# DP_current_measure_V3_extension.net
KiCad netlist of a schematic drawn in EAGLE
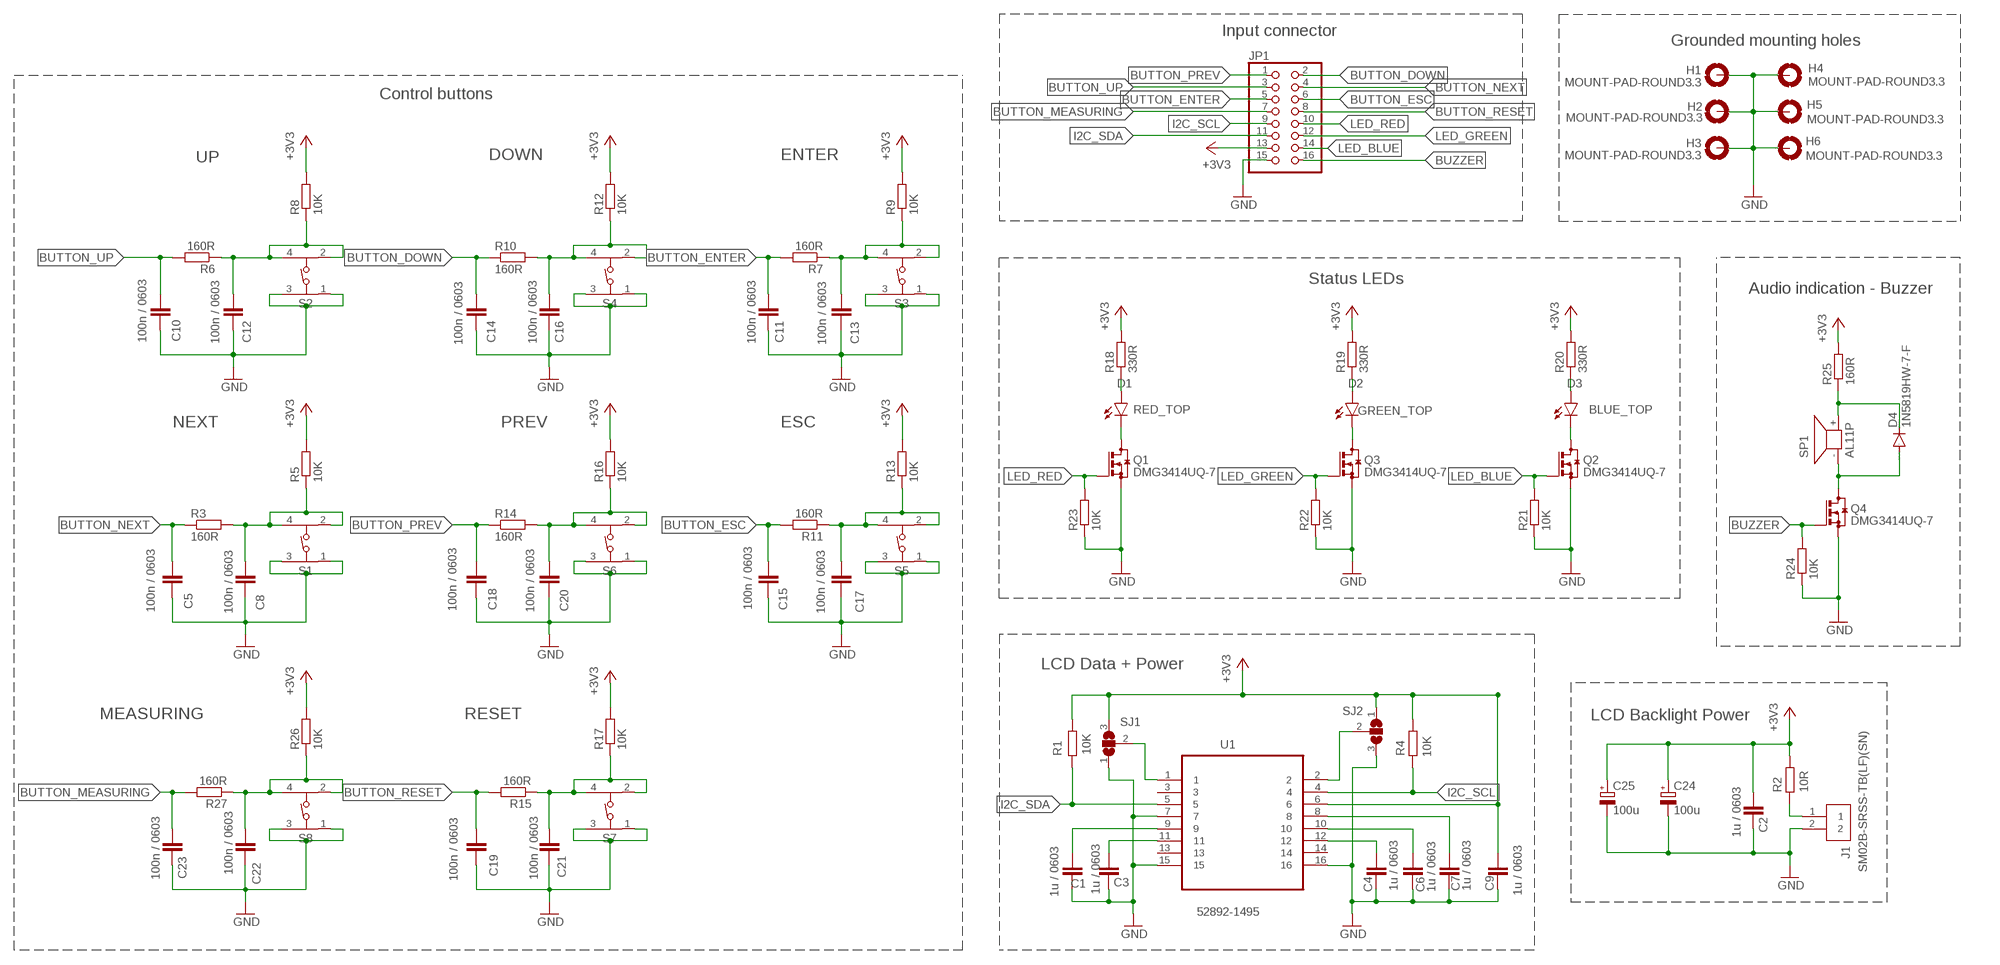
[diagram p0: schematic, sheet 1]

(export (version "E")
  (design (tool "Eeschema 10.0.6"))
  (components
    (comp (ref "C1")
      (value "1u / 0603")
      (footprint "eagle-import:C0603")
      (libsource (lib "eagle-import") (part "C-EUC0603"))
    )
    (comp (ref "C2")
      (value "1u / 0603")
      (footprint "eagle-import:C0603")
      (libsource (lib "eagle-import") (part "C-EUC0603"))
    )
    (comp (ref "C3")
      (value "1u / 0603")
      (footprint "eagle-import:C0603")
      (libsource (lib "eagle-import") (part "C-EUC0603"))
    )
    (comp (ref "C4")
      (value "1u / 0603")
      (footprint "eagle-import:C0603")
      (libsource (lib "eagle-import") (part "C-EUC0603"))
    )
    (comp (ref "C5")
      (value "100n / 0603")
      (footprint "eagle-import:C0603")
      (libsource (lib "eagle-import") (part "C-EUC0603"))
    )
    (comp (ref "C6")
      (value "1u / 0603")
      (footprint "eagle-import:C0603")
      (libsource (lib "eagle-import") (part "C-EUC0603"))
    )
    (comp (ref "C7")
      (value "1u / 0603")
      (footprint "eagle-import:C0603")
      (libsource (lib "eagle-import") (part "C-EUC0603"))
    )
    (comp (ref "C8")
      (value "100n / 0603")
      (footprint "eagle-import:C0603")
      (libsource (lib "eagle-import") (part "C-EUC0603"))
    )
    (comp (ref "C9")
      (value "1u / 0603")
      (footprint "eagle-import:C0603")
      (libsource (lib "eagle-import") (part "C-EUC0603"))
    )
    (comp (ref "C10")
      (value "100n / 0603")
      (footprint "eagle-import:C0603")
      (libsource (lib "eagle-import") (part "C-EUC0603"))
    )
    (comp (ref "C11")
      (value "100n / 0603")
      (footprint "eagle-import:C0603")
      (libsource (lib "eagle-import") (part "C-EUC0603"))
    )
    (comp (ref "C12")
      (value "100n / 0603")
      (footprint "eagle-import:C0603")
      (libsource (lib "eagle-import") (part "C-EUC0603"))
    )
    (comp (ref "C13")
      (value "100n / 0603")
      (footprint "eagle-import:C0603")
      (libsource (lib "eagle-import") (part "C-EUC0603"))
    )
    (comp (ref "C14")
      (value "100n / 0603")
      (footprint "eagle-import:C0603")
      (libsource (lib "eagle-import") (part "C-EUC0603"))
    )
    (comp (ref "C15")
      (value "100n / 0603")
      (footprint "eagle-import:C0603")
      (libsource (lib "eagle-import") (part "C-EUC0603"))
    )
    (comp (ref "C16")
      (value "100n / 0603")
      (footprint "eagle-import:C0603")
      (libsource (lib "eagle-import") (part "C-EUC0603"))
    )
    (comp (ref "C17")
      (value "100n / 0603")
      (footprint "eagle-import:C0603")
      (libsource (lib "eagle-import") (part "C-EUC0603"))
    )
    (comp (ref "C18")
      (value "100n / 0603")
      (footprint "eagle-import:C0603")
      (libsource (lib "eagle-import") (part "C-EUC0603"))
    )
    (comp (ref "C19")
      (value "100n / 0603")
      (footprint "eagle-import:C0603")
      (libsource (lib "eagle-import") (part "C-EUC0603"))
    )
    (comp (ref "C20")
      (value "100n / 0603")
      (footprint "eagle-import:C0603")
      (libsource (lib "eagle-import") (part "C-EUC0603"))
    )
    (comp (ref "C21")
      (value "100n / 0603")
      (footprint "eagle-import:C0603")
      (libsource (lib "eagle-import") (part "C-EUC0603"))
    )
    (comp (ref "C22")
      (value "100n / 0603")
      (footprint "eagle-import:C0603")
      (libsource (lib "eagle-import") (part "C-EUC0603"))
    )
    (comp (ref "C23")
      (value "100n / 0603")
      (footprint "eagle-import:C0603")
      (libsource (lib "eagle-import") (part "C-EUC0603"))
    )
    (comp (ref "C24")
      (value "100u")
      (footprint "eagle-import:SMC_B")
      (libsource (lib "eagle-import") (part "CPOL-EUSMCB"))
    )
    (comp (ref "C25")
      (value "100u")
      (footprint "eagle-import:SMC_B")
      (libsource (lib "eagle-import") (part "CPOL-EUSMCB"))
    )
    (comp (ref "D1")
      (value "RED_TOP")
      (footprint "eagle-import:LED-0603")
      (fields
        (field (name "DIGIKEY_PART_NUMBER") "160-1436-1-ND")
        (field (name "MANUFACTURER") "Lite-On Inc.")
        (field (name "MPN") "LTST-C190KRKT")
        (field (name "CREATED_BY") "PCBLayout.com")
      )
      (libsource (lib "eagle-import") (part "LTST-C190KRKT"))
    )
    (comp (ref "D2")
      (value "GREEN_TOP")
      (footprint "eagle-import:LED-0603")
      (fields
        (field (name "DIGIKEY_PART_NUMBER") "160-1436-1-ND")
        (field (name "MANUFACTURER") "Lite-On Inc.")
        (field (name "MPN") "LTST-C190KRKT")
        (field (name "CREATED_BY") "PCBLayout.com")
      )
      (libsource (lib "eagle-import") (part "LTST-C190KRKT"))
    )
    (comp (ref "D3")
      (value "BLUE_TOP")
      (footprint "eagle-import:LED-0603")
      (fields
        (field (name "DIGIKEY_PART_NUMBER") "160-1436-1-ND")
        (field (name "MANUFACTURER") "Lite-On Inc.")
        (field (name "MPN") "LTST-C190KRKT")
        (field (name "CREATED_BY") "PCBLayout.com")
      )
      (libsource (lib "eagle-import") (part "LTST-C190KRKT"))
    )
    (comp (ref "D4")
      (value "1N5819HW-7-F")
      (footprint "eagle-import:SOD-123_MINI-SMA")
      (libsource (lib "eagle-import") (part "CGRM400-G1"))
    )
    (comp (ref "H1")
      (value "MOUNT-PAD-ROUND3.3")
      (footprint "eagle-import:3,3-PAD")
      (libsource (lib "eagle-import") (part "MOUNT-PAD-ROUND3.3"))
    )
    (comp (ref "H2")
      (value "MOUNT-PAD-ROUND3.3")
      (footprint "eagle-import:3,3-PAD")
      (libsource (lib "eagle-import") (part "MOUNT-PAD-ROUND3.3"))
    )
    (comp (ref "H3")
      (value "MOUNT-PAD-ROUND3.3")
      (footprint "eagle-import:3,3-PAD")
      (libsource (lib "eagle-import") (part "MOUNT-PAD-ROUND3.3"))
    )
    (comp (ref "H4")
      (value "MOUNT-PAD-ROUND3.3")
      (footprint "eagle-import:3,3-PAD")
      (libsource (lib "eagle-import") (part "MOUNT-PAD-ROUND3.3"))
    )
    (comp (ref "H5")
      (value "MOUNT-PAD-ROUND3.3")
      (footprint "eagle-import:3,3-PAD")
      (libsource (lib "eagle-import") (part "MOUNT-PAD-ROUND3.3"))
    )
    (comp (ref "H6")
      (value "MOUNT-PAD-ROUND3.3")
      (footprint "eagle-import:3,3-PAD")
      (libsource (lib "eagle-import") (part "MOUNT-PAD-ROUND3.3"))
    )
    (comp (ref "J1")
      (value "SM02B-SRSS-TB(LF)(SN)")
      (footprint "eagle-import:SM02B-SRSS-TB(LF)(SN)")
      (fields (field (name "MF") "JST Sales") (field (name "MP") "SM02B-SRSS-TB_LF__SN_"))
      (libsource (lib "eagle-import") (part "SM02B-SRSS-TB(LF)(SN)"))
    )
    (comp (ref "JP1")
      (value "PINHD-2X8")
      (footprint "eagle-import:2X08")
      (libsource (lib "eagle-import") (part "PINHD-2X8"))
    )
    (comp (ref "Q1")
      (value "DMG3414UQ-7")
      (footprint "eagle-import:SOT23")
      (libsource (lib "eagle-import") (part "BSS123"))
    )
    (comp (ref "Q2")
      (value "DMG3414UQ-7")
      (footprint "eagle-import:SOT23")
      (libsource (lib "eagle-import") (part "BSS123"))
    )
    (comp (ref "Q3")
      (value "DMG3414UQ-7")
      (footprint "eagle-import:SOT23")
      (libsource (lib "eagle-import") (part "BSS123"))
    )
    (comp (ref "Q4")
      (value "DMG3414UQ-7")
      (footprint "eagle-import:SOT23")
      (libsource (lib "eagle-import") (part "BSS123"))
    )
    (comp (ref "R1")
      (value "10K")
      (footprint "eagle-import:R0603")
      (libsource (lib "eagle-import") (part "R-EU_R0603"))
    )
    (comp (ref "R2")
      (value "10R")
      (footprint "eagle-import:R0603")
      (libsource (lib "eagle-import") (part "R-EU_R0603"))
    )
    (comp (ref "R3")
      (value "160R")
      (footprint "eagle-import:R0603")
      (libsource (lib "eagle-import") (part "R-EU_R0603"))
    )
    (comp (ref "R4")
      (value "10K")
      (footprint "eagle-import:R0603")
      (libsource (lib "eagle-import") (part "R-EU_R0603"))
    )
    (comp (ref "R5")
      (value "10K")
      (footprint "eagle-import:R0603")
      (libsource (lib "eagle-import") (part "R-EU_R0603"))
    )
    (comp (ref "R6")
      (value "160R")
      (footprint "eagle-import:R0603")
      (libsource (lib "eagle-import") (part "R-EU_R0603"))
    )
    (comp (ref "R7")
      (value "160R")
      (footprint "eagle-import:R0603")
      (libsource (lib "eagle-import") (part "R-EU_R0603"))
    )
    (comp (ref "R8")
      (value "10K")
      (footprint "eagle-import:R0603")
      (libsource (lib "eagle-import") (part "R-EU_R0603"))
    )
    (comp (ref "R9")
      (value "10K")
      (footprint "eagle-import:R0603")
      (libsource (lib "eagle-import") (part "R-EU_R0603"))
    )
    (comp (ref "R10")
      (value "160R")
      (footprint "eagle-import:R0603")
      (libsource (lib "eagle-import") (part "R-EU_R0603"))
    )
    (comp (ref "R11")
      (value "160R")
      (footprint "eagle-import:R0603")
      (libsource (lib "eagle-import") (part "R-EU_R0603"))
    )
    (comp (ref "R12")
      (value "10K")
      (footprint "eagle-import:R0603")
      (libsource (lib "eagle-import") (part "R-EU_R0603"))
    )
    (comp (ref "R13")
      (value "10K")
      (footprint "eagle-import:R0603")
      (libsource (lib "eagle-import") (part "R-EU_R0603"))
    )
    (comp (ref "R14")
      (value "160R")
      (footprint "eagle-import:R0603")
      (libsource (lib "eagle-import") (part "R-EU_R0603"))
    )
    (comp (ref "R15")
      (value "160R")
      (footprint "eagle-import:R0603")
      (libsource (lib "eagle-import") (part "R-EU_R0603"))
    )
    (comp (ref "R16")
      (value "10K")
      (footprint "eagle-import:R0603")
      (libsource (lib "eagle-import") (part "R-EU_R0603"))
    )
    (comp (ref "R17")
      (value "10K")
      (footprint "eagle-import:R0603")
      (libsource (lib "eagle-import") (part "R-EU_R0603"))
    )
    (comp (ref "R18")
      (value "330R")
      (footprint "eagle-import:R0603")
      (libsource (lib "eagle-import") (part "R-EU_R0603"))
    )
    (comp (ref "R19")
      (value "330R")
      (footprint "eagle-import:R0603")
      (libsource (lib "eagle-import") (part "R-EU_R0603"))
    )
    (comp (ref "R20")
      (value "330R")
      (footprint "eagle-import:R0603")
      (libsource (lib "eagle-import") (part "R-EU_R0603"))
    )
    (comp (ref "R21")
      (value "10K")
      (footprint "eagle-import:R0603")
      (libsource (lib "eagle-import") (part "R-EU_R0603"))
    )
    (comp (ref "R22")
      (value "10K")
      (footprint "eagle-import:R0603")
      (libsource (lib "eagle-import") (part "R-EU_R0603"))
    )
    (comp (ref "R23")
      (value "10K")
      (footprint "eagle-import:R0603")
      (libsource (lib "eagle-import") (part "R-EU_R0603"))
    )
    (comp (ref "R24")
      (value "10K")
      (footprint "eagle-import:R0603")
      (libsource (lib "eagle-import") (part "R-EU_R0603"))
    )
    (comp (ref "R25")
      (value "160R")
      (footprint "eagle-import:R0603")
      (libsource (lib "eagle-import") (part "R-EU_R0603"))
    )
    (comp (ref "R26")
      (value "10K")
      (footprint "eagle-import:R0603")
      (libsource (lib "eagle-import") (part "R-EU_R0603"))
    )
    (comp (ref "R27")
      (value "160R")
      (footprint "eagle-import:R0603")
      (libsource (lib "eagle-import") (part "R-EU_R0603"))
    )
    (comp (ref "S1")
      (value "430152095826")
      (footprint "eagle-import:430152095826")
      (libsource (lib "eagle-import") (part "430152095826"))
    )
    (comp (ref "S2")
      (value "430152095826")
      (footprint "eagle-import:430152095826")
      (libsource (lib "eagle-import") (part "430152095826"))
    )
    (comp (ref "S3")
      (value "430152095826")
      (footprint "eagle-import:430152095826")
      (libsource (lib "eagle-import") (part "430152095826"))
    )
    (comp (ref "S4")
      (value "430152095826")
      (footprint "eagle-import:430152095826")
      (libsource (lib "eagle-import") (part "430152095826"))
    )
    (comp (ref "S5")
      (value "430152095826")
      (footprint "eagle-import:430152095826")
      (libsource (lib "eagle-import") (part "430152095826"))
    )
    (comp (ref "S6")
      (value "430152095826")
      (footprint "eagle-import:430152095826")
      (libsource (lib "eagle-import") (part "430152095826"))
    )
    (comp (ref "S7")
      (value "430152095826")
      (footprint "eagle-import:430152095826")
      (libsource (lib "eagle-import") (part "430152095826"))
    )
    (comp (ref "S8")
      (value "430152095826")
      (footprint "eagle-import:430152095826")
      (libsource (lib "eagle-import") (part "430152095826"))
    )
    (comp (ref "SJ1")
      (value "SJ2W")
      (footprint "eagle-import:SJ_2")
      (libsource (lib "eagle-import") (part "SJ2W"))
    )
    (comp (ref "SJ2")
      (value "SJ2W")
      (footprint "eagle-import:SJ_2")
      (libsource (lib "eagle-import") (part "SJ2W"))
    )
    (comp (ref "SP1")
      (value "AL11P")
      (footprint "eagle-import:AL11P")
      (libsource (lib "eagle-import") (part "AL11P"))
    )
    (comp (ref "U1")
      (value "52892-1495")
      (footprint "eagle-import:MOLEX_52892-1495")
      (fields (field (name "MF") "Molex Connector"))
      (libsource (lib "eagle-import") (part "52892-1495"))
    )
  )
  (nets
    (net (code "1") (name "+3V3") (class "Default")
      (node (ref "C2") (pin "1") (pinfunction "1_1") (pintype "passive"))
      (node (ref "C24") (pin "+") (pinfunction "+_+") (pintype "passive"))
      (node (ref "C25") (pin "+") (pinfunction "+_+") (pintype "passive"))
      (node (ref "C9") (pin "1") (pinfunction "1_1") (pintype "passive"))
      (node (ref "JP1") (pin "13") (pinfunction "13_13") (pintype "passive"))
      (node (ref "R1") (pin "2") (pinfunction "2_2") (pintype "passive"))
      (node (ref "R12") (pin "2") (pinfunction "2_2") (pintype "passive"))
      (node (ref "R13") (pin "2") (pinfunction "2_2") (pintype "passive"))
      (node (ref "R16") (pin "2") (pinfunction "2_2") (pintype "passive"))
      (node (ref "R17") (pin "2") (pinfunction "2_2") (pintype "passive"))
      (node (ref "R18") (pin "2") (pinfunction "2_2") (pintype "passive"))
      (node (ref "R19") (pin "2") (pinfunction "2_2") (pintype "passive"))
      (node (ref "R2") (pin "2") (pinfunction "2_2") (pintype "passive"))
      (node (ref "R20") (pin "2") (pinfunction "2_2") (pintype "passive"))
      (node (ref "R25") (pin "2") (pinfunction "2_2") (pintype "passive"))
      (node (ref "R26") (pin "2") (pinfunction "2_2") (pintype "passive"))
      (node (ref "R4") (pin "2") (pinfunction "2_2") (pintype "passive"))
      (node (ref "R5") (pin "2") (pinfunction "2_2") (pintype "passive"))
      (node (ref "R8") (pin "2") (pinfunction "2_2") (pintype "passive"))
      (node (ref "R9") (pin "2") (pinfunction "2_2") (pintype "passive"))
      (node (ref "SJ1") (pin "3") (pinfunction "3_3") (pintype "passive"))
      (node (ref "SJ2") (pin "1") (pinfunction "1_1") (pintype "passive"))
      (node (ref "U1") (pin "6") (pinfunction "6_6") (pintype "passive"))
    )
    (net (code "2") (name "BUTTON_DOWN") (class "Default")
      (node (ref "C14") (pin "1") (pinfunction "1_1") (pintype "passive"))
      (node (ref "JP1") (pin "2") (pinfunction "2_2") (pintype "passive"))
      (node (ref "R10") (pin "1") (pinfunction "1_1") (pintype "passive"))
    )
    (net (code "3") (name "BUTTON_ENTER") (class "Default")
      (node (ref "C11") (pin "1") (pinfunction "1_1") (pintype "passive"))
      (node (ref "JP1") (pin "5") (pinfunction "5_5") (pintype "passive"))
      (node (ref "R7") (pin "2") (pinfunction "2_2") (pintype "passive"))
    )
    (net (code "4") (name "BUTTON_ESC") (class "Default")
      (node (ref "C15") (pin "1") (pinfunction "1_1") (pintype "passive"))
      (node (ref "JP1") (pin "6") (pinfunction "6_6") (pintype "passive"))
      (node (ref "R11") (pin "2") (pinfunction "2_2") (pintype "passive"))
    )
    (net (code "5") (name "BUTTON_MEASURING") (class "Default")
      (node (ref "C23") (pin "1") (pinfunction "1_1") (pintype "passive"))
      (node (ref "JP1") (pin "7") (pinfunction "7_7") (pintype "passive"))
      (node (ref "R27") (pin "2") (pinfunction "2_2") (pintype "passive"))
    )
    (net (code "6") (name "BUTTON_NEXT") (class "Default")
      (node (ref "C5") (pin "1") (pinfunction "1_1") (pintype "passive"))
      (node (ref "JP1") (pin "4") (pinfunction "4_4") (pintype "passive"))
      (node (ref "R3") (pin "1") (pinfunction "1_1") (pintype "passive"))
    )
    (net (code "7") (name "BUTTON_PREV") (class "Default")
      (node (ref "C18") (pin "1") (pinfunction "1_1") (pintype "passive"))
      (node (ref "JP1") (pin "1") (pinfunction "1_1") (pintype "passive"))
      (node (ref "R14") (pin "1") (pinfunction "1_1") (pintype "passive"))
    )
    (net (code "8") (name "BUTTON_RESET") (class "Default")
      (node (ref "C19") (pin "1") (pinfunction "1_1") (pintype "passive"))
      (node (ref "JP1") (pin "8") (pinfunction "8_8") (pintype "passive"))
      (node (ref "R15") (pin "2") (pinfunction "2_2") (pintype "passive"))
    )
    (net (code "9") (name "BUTTON_UP") (class "Default")
      (node (ref "C10") (pin "1") (pinfunction "1_1") (pintype "passive"))
      (node (ref "JP1") (pin "3") (pinfunction "3_3") (pintype "passive"))
      (node (ref "R6") (pin "2") (pinfunction "2_2") (pintype "passive"))
    )
    (net (code "10") (name "BUZZER") (class "Default")
      (node (ref "JP1") (pin "16") (pinfunction "16_16") (pintype "passive"))
      (node (ref "Q4") (pin "1") (pinfunction "G_1") (pintype "passive"))
      (node (ref "R24") (pin "2") (pinfunction "2_2") (pintype "passive"))
    )
    (net (code "11") (name "GND") (class "Default")
      (node (ref "C1") (pin "2") (pinfunction "2_2") (pintype "passive"))
      (node (ref "C10") (pin "2") (pinfunction "2_2") (pintype "passive"))
      (node (ref "C11") (pin "2") (pinfunction "2_2") (pintype "passive"))
      (node (ref "C12") (pin "2") (pinfunction "2_2") (pintype "passive"))
      (node (ref "C13") (pin "2") (pinfunction "2_2") (pintype "passive"))
      (node (ref "C14") (pin "2") (pinfunction "2_2") (pintype "passive"))
      (node (ref "C15") (pin "2") (pinfunction "2_2") (pintype "passive"))
      (node (ref "C16") (pin "2") (pinfunction "2_2") (pintype "passive"))
      (node (ref "C17") (pin "2") (pinfunction "2_2") (pintype "passive"))
      (node (ref "C18") (pin "2") (pinfunction "2_2") (pintype "passive"))
      (node (ref "C19") (pin "2") (pinfunction "2_2") (pintype "passive"))
      (node (ref "C2") (pin "2") (pinfunction "2_2") (pintype "passive"))
      (node (ref "C20") (pin "2") (pinfunction "2_2") (pintype "passive"))
      (node (ref "C21") (pin "2") (pinfunction "2_2") (pintype "passive"))
      (node (ref "C22") (pin "2") (pinfunction "2_2") (pintype "passive"))
      (node (ref "C23") (pin "2") (pinfunction "2_2") (pintype "passive"))
      (node (ref "C24") (pin "-") (pinfunction "-_-") (pintype "passive"))
      (node (ref "C25") (pin "-") (pinfunction "-_-") (pintype "passive"))
      (node (ref "C3") (pin "2") (pinfunction "2_2") (pintype "passive"))
      (node (ref "C4") (pin "2") (pinfunction "2_2") (pintype "passive"))
      (node (ref "C5") (pin "2") (pinfunction "2_2") (pintype "passive"))
      (node (ref "C6") (pin "2") (pinfunction "2_2") (pintype "passive"))
      (node (ref "C7") (pin "2") (pinfunction "2_2") (pintype "passive"))
      (node (ref "C8") (pin "2") (pinfunction "2_2") (pintype "passive"))
      (node (ref "C9") (pin "2") (pinfunction "2_2") (pintype "passive"))
      (node (ref "H1") (pin "B3,3") (pinfunction "MOUNT_B3,3") (pintype "passive"))
      (node (ref "H2") (pin "B3,3") (pinfunction "MOUNT_B3,3") (pintype "passive"))
      (node (ref "H3") (pin "B3,3") (pinfunction "MOUNT_B3,3") (pintype "passive"))
      (node (ref "H4") (pin "B3,3") (pinfunction "MOUNT_B3,3") (pintype "passive"))
      (node (ref "H5") (pin "B3,3") (pinfunction "MOUNT_B3,3") (pintype "passive"))
      (node (ref "H6") (pin "B3,3") (pinfunction "MOUNT_B3,3") (pintype "passive"))
      (node (ref "J1") (pin "2") (pinfunction "2_2") (pintype "bidirectional"))
      (node (ref "JP1") (pin "15") (pinfunction "15_15") (pintype "passive"))
      (node (ref "Q1") (pin "2") (pinfunction "S_2") (pintype "passive"))
      (node (ref "Q2") (pin "2") (pinfunction "S_2") (pintype "passive"))
      (node (ref "Q3") (pin "2") (pinfunction "S_2") (pintype "passive"))
      (node (ref "Q4") (pin "2") (pinfunction "S_2") (pintype "passive"))
      (node (ref "R21") (pin "1") (pinfunction "1_1") (pintype "passive"))
      (node (ref "R22") (pin "1") (pinfunction "1_1") (pintype "passive"))
      (node (ref "R23") (pin "1") (pinfunction "1_1") (pintype "passive"))
      (node (ref "R24") (pin "1") (pinfunction "1_1") (pintype "passive"))
      (node (ref "S1") (pin "1") (pinfunction "1_1") (pintype "passive"))
      (node (ref "S1") (pin "3") (pinfunction "3_3") (pintype "passive"))
      (node (ref "S2") (pin "1") (pinfunction "1_1") (pintype "passive"))
      (node (ref "S2") (pin "3") (pinfunction "3_3") (pintype "passive"))
      (node (ref "S3") (pin "1") (pinfunction "1_1") (pintype "passive"))
      (node (ref "S3") (pin "3") (pinfunction "3_3") (pintype "passive"))
      (node (ref "S4") (pin "1") (pinfunction "1_1") (pintype "passive"))
      (node (ref "S4") (pin "3") (pinfunction "3_3") (pintype "passive"))
      (node (ref "S5") (pin "1") (pinfunction "1_1") (pintype "passive"))
      (node (ref "S5") (pin "3") (pinfunction "3_3") (pintype "passive"))
      (node (ref "S6") (pin "1") (pinfunction "1_1") (pintype "passive"))
      (node (ref "S6") (pin "3") (pinfunction "3_3") (pintype "passive"))
      (node (ref "S7") (pin "1") (pinfunction "1_1") (pintype "passive"))
      (node (ref "S7") (pin "3") (pinfunction "3_3") (pintype "passive"))
      (node (ref "S8") (pin "1") (pinfunction "1_1") (pintype "passive"))
      (node (ref "S8") (pin "3") (pinfunction "3_3") (pintype "passive"))
      (node (ref "SJ1") (pin "1") (pinfunction "1_1") (pintype "passive"))
      (node (ref "SJ2") (pin "3") (pinfunction "3_3") (pintype "passive"))
      (node (ref "U1") (pin "15") (pinfunction "15_15") (pintype "passive"))
      (node (ref "U1") (pin "16") (pinfunction "16_16") (pintype "passive"))
      (node (ref "U1") (pin "7") (pinfunction "7_7") (pintype "passive"))
    )
    (net (code "12") (name "I2C_SCL") (class "Default")
      (node (ref "JP1") (pin "9") (pinfunction "9_9") (pintype "passive"))
      (node (ref "R4") (pin "1") (pinfunction "1_1") (pintype "passive"))
      (node (ref "U1") (pin "4") (pinfunction "4_4") (pintype "passive"))
    )
    (net (code "13") (name "I2C_SDA") (class "Default")
      (node (ref "JP1") (pin "11") (pinfunction "11_11") (pintype "passive"))
      (node (ref "R1") (pin "1") (pinfunction "1_1") (pintype "passive"))
      (node (ref "U1") (pin "5") (pinfunction "5_5") (pintype "passive"))
    )
    (net (code "14") (name "LED_BLUE") (class "Default")
      (node (ref "JP1") (pin "14") (pinfunction "14_14") (pintype "passive"))
      (node (ref "Q2") (pin "1") (pinfunction "G_1") (pintype "passive"))
      (node (ref "R21") (pin "2") (pinfunction "2_2") (pintype "passive"))
    )
    (net (code "15") (name "LED_GREEN") (class "Default")
      (node (ref "JP1") (pin "12") (pinfunction "12_12") (pintype "passive"))
      (node (ref "Q3") (pin "1") (pinfunction "G_1") (pintype "passive"))
      (node (ref "R22") (pin "2") (pinfunction "2_2") (pintype "passive"))
    )
    (net (code "16") (name "LED_RED") (class "Default")
      (node (ref "JP1") (pin "10") (pinfunction "10_10") (pintype "passive"))
      (node (ref "Q1") (pin "1") (pinfunction "G_1") (pintype "passive"))
      (node (ref "R23") (pin "2") (pinfunction "2_2") (pintype "passive"))
    )
    (net (code "17") (name "Net-(C1-Pad1)") (class "Default")
      (node (ref "C1") (pin "1") (pinfunction "1_1") (pintype "passive"))
      (node (ref "U1") (pin "9") (pinfunction "9_9") (pintype "passive"))
    )
    (net (code "18") (name "Net-(C3-Pad1)") (class "Default")
      (node (ref "C3") (pin "1") (pinfunction "1_1") (pintype "passive"))
      (node (ref "U1") (pin "11") (pinfunction "11_11") (pintype "passive"))
    )
    (net (code "19") (name "Net-(C4-Pad1)") (class "Default")
      (node (ref "C4") (pin "1") (pinfunction "1_1") (pintype "passive"))
      (node (ref "U1") (pin "12") (pinfunction "12_12") (pintype "passive"))
    )
    (net (code "20") (name "Net-(C6-Pad1)") (class "Default")
      (node (ref "C6") (pin "1") (pinfunction "1_1") (pintype "passive"))
      (node (ref "U1") (pin "10") (pinfunction "10_10") (pintype "passive"))
    )
    (net (code "21") (name "Net-(C7-Pad1)") (class "Default")
      (node (ref "C7") (pin "1") (pinfunction "1_1") (pintype "passive"))
      (node (ref "U1") (pin "8") (pinfunction "8_8") (pintype "passive"))
    )
    (net (code "22") (name "Net-(C8-Pad1)") (class "Default")
      (node (ref "C8") (pin "1") (pinfunction "1_1") (pintype "passive"))
      (node (ref "R3") (pin "2") (pinfunction "2_2") (pintype "passive"))
      (node (ref "R5") (pin "1") (pinfunction "1_1") (pintype "passive"))
      (node (ref "S1") (pin "2") (pinfunction "2_2") (pintype "passive"))
      (node (ref "S1") (pin "4") (pinfunction "4_4") (pintype "passive"))
    )
    (net (code "23") (name "Net-(C12-Pad1)") (class "Default")
      (node (ref "C12") (pin "1") (pinfunction "1_1") (pintype "passive"))
      (node (ref "R6") (pin "1") (pinfunction "1_1") (pintype "passive"))
      (node (ref "R8") (pin "1") (pinfunction "1_1") (pintype "passive"))
      (node (ref "S2") (pin "2") (pinfunction "2_2") (pintype "passive"))
      (node (ref "S2") (pin "4") (pinfunction "4_4") (pintype "passive"))
    )
    (net (code "24") (name "Net-(C13-Pad1)") (class "Default")
      (node (ref "C13") (pin "1") (pinfunction "1_1") (pintype "passive"))
      (node (ref "R7") (pin "1") (pinfunction "1_1") (pintype "passive"))
      (node (ref "R9") (pin "1") (pinfunction "1_1") (pintype "passive"))
      (node (ref "S3") (pin "2") (pinfunction "2_2") (pintype "passive"))
      (node (ref "S3") (pin "4") (pinfunction "4_4") (pintype "passive"))
    )
    (net (code "25") (name "Net-(C16-Pad1)") (class "Default")
      (node (ref "C16") (pin "1") (pinfunction "1_1") (pintype "passive"))
      (node (ref "R10") (pin "2") (pinfunction "2_2") (pintype "passive"))
      (node (ref "R12") (pin "1") (pinfunction "1_1") (pintype "passive"))
      (node (ref "S4") (pin "2") (pinfunction "2_2") (pintype "passive"))
      (node (ref "S4") (pin "4") (pinfunction "4_4") (pintype "passive"))
    )
    (net (code "26") (name "Net-(C17-Pad1)") (class "Default")
      (node (ref "C17") (pin "1") (pinfunction "1_1") (pintype "passive"))
      (node (ref "R11") (pin "1") (pinfunction "1_1") (pintype "passive"))
      (node (ref "R13") (pin "1") (pinfunction "1_1") (pintype "passive"))
      (node (ref "S5") (pin "2") (pinfunction "2_2") (pintype "passive"))
      (node (ref "S5") (pin "4") (pinfunction "4_4") (pintype "passive"))
    )
    (net (code "27") (name "Net-(C20-Pad1)") (class "Default")
      (node (ref "C20") (pin "1") (pinfunction "1_1") (pintype "passive"))
      (node (ref "R14") (pin "2") (pinfunction "2_2") (pintype "passive"))
      (node (ref "R16") (pin "1") (pinfunction "1_1") (pintype "passive"))
      (node (ref "S6") (pin "2") (pinfunction "2_2") (pintype "passive"))
      (node (ref "S6") (pin "4") (pinfunction "4_4") (pintype "passive"))
    )
    (net (code "28") (name "Net-(C21-Pad1)") (class "Default")
      (node (ref "C21") (pin "1") (pinfunction "1_1") (pintype "passive"))
      (node (ref "R15") (pin "1") (pinfunction "1_1") (pintype "passive"))
      (node (ref "R17") (pin "1") (pinfunction "1_1") (pintype "passive"))
      (node (ref "S7") (pin "2") (pinfunction "2_2") (pintype "passive"))
      (node (ref "S7") (pin "4") (pinfunction "4_4") (pintype "passive"))
    )
    (net (code "29") (name "Net-(C22-Pad1)") (class "Default")
      (node (ref "C22") (pin "1") (pinfunction "1_1") (pintype "passive"))
      (node (ref "R26") (pin "1") (pinfunction "1_1") (pintype "passive"))
      (node (ref "R27") (pin "1") (pinfunction "1_1") (pintype "passive"))
      (node (ref "S8") (pin "2") (pinfunction "2_2") (pintype "passive"))
      (node (ref "S8") (pin "4") (pinfunction "4_4") (pintype "passive"))
    )
    (net (code "30") (name "Net-(D1-PadA)") (class "Default")
      (node (ref "D1") (pin "A") (pinfunction "A_A") (pintype "passive"))
      (node (ref "R18") (pin "1") (pinfunction "1_1") (pintype "passive"))
    )
    (net (code "31") (name "Net-(D2-PadA)") (class "Default")
      (node (ref "D2") (pin "A") (pinfunction "A_A") (pintype "passive"))
      (node (ref "R19") (pin "1") (pinfunction "1_1") (pintype "passive"))
    )
    (net (code "32") (name "Net-(D3-PadA)") (class "Default")
      (node (ref "D3") (pin "A") (pinfunction "A_A") (pintype "passive"))
      (node (ref "R20") (pin "1") (pinfunction "1_1") (pintype "passive"))
    )
    (net (code "33") (name "Net-(J1-Pad1)") (class "Default")
      (node (ref "J1") (pin "1") (pinfunction "1_1") (pintype "bidirectional"))
      (node (ref "R2") (pin "1") (pinfunction "1_1") (pintype "passive"))
    )
    (net (code "34") (name "Net-(Q1-D)") (class "Default")
      (node (ref "D1") (pin "C") (pinfunction "C_C") (pintype "passive"))
      (node (ref "Q1") (pin "3") (pinfunction "D_3") (pintype "passive"))
    )
    (net (code "35") (name "Net-(Q2-D)") (class "Default")
      (node (ref "D3") (pin "C") (pinfunction "C_C") (pintype "passive"))
      (node (ref "Q2") (pin "3") (pinfunction "D_3") (pintype "passive"))
    )
    (net (code "36") (name "Net-(Q3-D)") (class "Default")
      (node (ref "D2") (pin "C") (pinfunction "C_C") (pintype "passive"))
      (node (ref "Q3") (pin "3") (pinfunction "D_3") (pintype "passive"))
    )
    (net (code "37") (name "Net-(Q4-D)") (class "Default")
      (node (ref "D4") (pin "A") (pinfunction "A_A") (pintype "passive"))
      (node (ref "Q4") (pin "3") (pinfunction "D_3") (pintype "passive"))
      (node (ref "SP1") (pin "-") (pinfunction "1_-") (pintype "passive"))
    )
    (net (code "38") (name "Net-(SJ1-Pad2)") (class "Default")
      (node (ref "SJ1") (pin "2") (pinfunction "2_2") (pintype "passive"))
      (node (ref "U1") (pin "1") (pinfunction "1_1") (pintype "passive"))
    )
    (net (code "39") (name "Net-(SJ2-Pad2)") (class "Default")
      (node (ref "SJ2") (pin "2") (pinfunction "2_2") (pintype "passive"))
      (node (ref "U1") (pin "2") (pinfunction "2_2") (pintype "passive"))
    )
    (net (code "40") (name "Net-(SP1-2)") (class "Default")
      (node (ref "D4") (pin "C") (pinfunction "C_C") (pintype "passive"))
      (node (ref "R25") (pin "1") (pinfunction "1_1") (pintype "passive"))
      (node (ref "SP1") (pin "+") (pinfunction "2_+") (pintype "passive"))
    )
    (net (code "41") (name "unconnected-(U1-Pad3)") (class "Default")
      (node (ref "U1") (pin "3") (pinfunction "3_3") (pintype "passive"))
    )
    (net (code "42") (name "unconnected-(U1-Pad13)") (class "Default")
      (node (ref "U1") (pin "13") (pinfunction "13_13") (pintype "passive"))
    )
    (net (code "43") (name "unconnected-(U1-Pad14)") (class "Default")
      (node (ref "U1") (pin "14") (pinfunction "14_14") (pintype "passive"))
    )
  )
)
